# Sheet1.net
KiCad netlist of a schematic drawn in Altium Designer
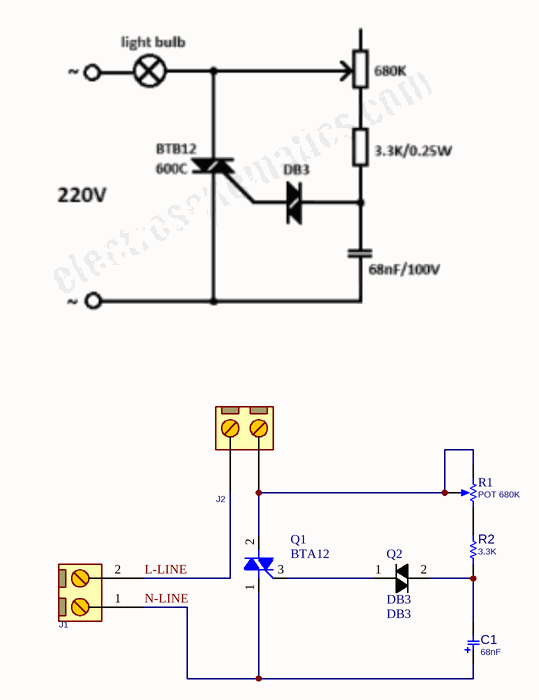
[diagram p0: Sheet1.SchDoc]

(export (version "E")
  (design (tool "Eeschema 10.0.6"))
  (components
    (comp (ref "C1")
      (value "68nF")
      (footprint "C_FLM_7X5X10")
      (description "CAP, THD, FILM,")
      (fields (field (name "MANF_P#") "MANF_PART#") (field (name "MANF") "MANF"))
      (libsource (lib "passive_thd") (part "CAP_THD_FLM"))
    )
    (comp (ref "J1")
      (value "CONN_TB2")
      (footprint "TBG_2")
      (description "CONN, TERMINAL BLOCK, 5.08mm pitch")
      (libsource (lib "") (part "CONN_TB2_1"))
    )
    (comp (ref "J2")
      (value "CONN_TB2")
      (footprint "TBG_2")
      (description "CONN, TERMINAL BLOCK, 5.08mm pitch")
      (libsource (lib "conn_terminalB") (part "CONN_TB2"))
    )
    (comp (ref "Q1")
      (value "BTA12")
      (footprint "TO220_3")
      (description "Triac, 600V, 12A, TO-220")
      (fields (field (name "MANF_P#") "BTA12-600BW, BTA12-600CW, BTA12-600TW") (field (name "MANF") "ST"))
      (libsource (lib "triac_diac") (part "TRIAC_BTA12-600_TO220"))
    )
    (comp (ref "Q2")
      (value "DB3")
      (footprint "D_AX03_DO35")
      (description "Diac, 32VBO, DO-35")
      (fields (field (name "MANF") "ST") (field (name "ALTIUM_VALUE") "DB3"))
      (libsource (lib "triac_diac") (part "DIAC_DB3_DO35"))
    )
    (comp (ref "R1")
      (value "POT 680K")
      (footprint "POT_7X5")
      (description "RESISTOR, THD, Potentiometer")
      (libsource (lib "resistor_pot_trimmer") (part "RES_THD_POT_7X5"))
    )
    (comp (ref "R2")
      (value "3.3K")
      (footprint "R025W_AX04")
      (description "RESISTOR, THD")
      (fields (field (name "MANF_P#") "RK73H1ETTP4701F") (field (name "MANF") "KOA SPEER"))
      (libsource (lib "passive_thd") (part "RES_THD"))
    )
  )
  (nets
    (net (code "1") (name "/L-LINE") (class "Default")
      (node (ref "J1") (pin "2") (pinfunction "2_2") (pintype "passive"))
      (node (ref "J2") (pin "1") (pinfunction "1_1") (pintype "passive"))
    )
    (net (code "2") (name "/N-LINE") (class "Default")
      (node (ref "C1") (pin "1") (pinfunction "1_1") (pintype "passive"))
      (node (ref "J1") (pin "1") (pinfunction "1_1") (pintype "passive"))
      (node (ref "Q1") (pin "1") (pinfunction "T1_1") (pintype "passive"))
    )
    (net (code "3") (name "Net-(Q1-G)") (class "Default")
      (node (ref "Q1") (pin "3") (pinfunction "G_3") (pintype "passive"))
      (node (ref "Q2") (pin "1") (pinfunction "A1_1") (pintype "passive"))
    )
    (net (code "4") (name "Net-(Q1-T2)") (class "Default")
      (node (ref "J2") (pin "2") (pinfunction "2_2") (pintype "passive"))
      (node (ref "Q1") (pin "2") (pinfunction "T2_2") (pintype "passive"))
      (node (ref "R1") (pin "1") (pinfunction "TOP_1") (pintype "passive"))
      (node (ref "R1") (pin "2") (pinfunction "TAP_2") (pintype "passive"))
    )
    (net (code "5") (name "Net-(Q2-A2)") (class "Default")
      (node (ref "C1") (pin "2") (pinfunction "2_2") (pintype "passive"))
      (node (ref "Q2") (pin "2") (pinfunction "A2_2") (pintype "passive"))
      (node (ref "R2") (pin "1") (pinfunction "1_1") (pintype "passive"))
    )
    (net (code "6") (name "Net-(R1-BOT)") (class "Default")
      (node (ref "R1") (pin "3") (pinfunction "BOT_3") (pintype "passive"))
      (node (ref "R2") (pin "2") (pinfunction "2_2") (pintype "passive"))
    )
  )
)
